# Power.net
KiCad netlist of a schematic drawn in Altium Designer
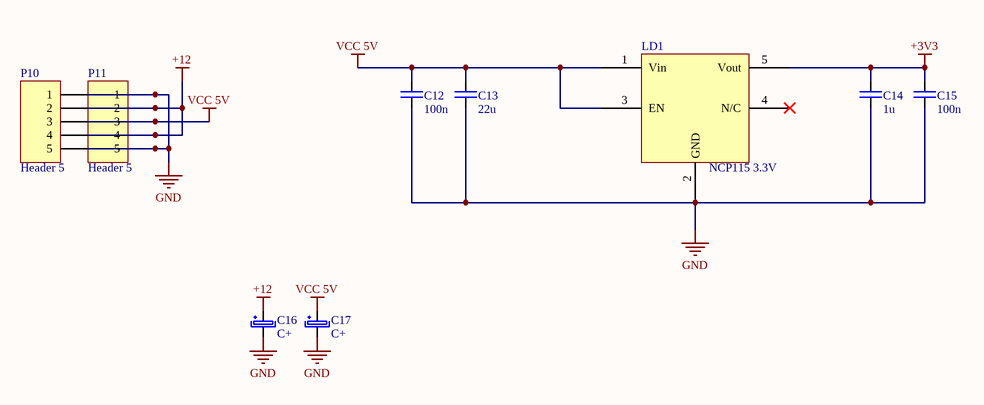
[diagram p0: Power.SchDoc]

(export (version "E")
  (design (tool "Eeschema 10.0.6"))
  (components
    (comp (ref "C12")
      (value "100n")
      (footprint "R1005_0402i_L")
      (description "Capacitor")
      (libsource (lib "General") (part "C"))
    )
    (comp (ref "C13")
      (value "22u")
      (footprint "C1608_0603I_L")
      (description "Capacitor")
      (libsource (lib "General") (part "C"))
    )
    (comp (ref "C14")
      (value "1u")
      (footprint "R1005_0402i_L")
      (description "Capacitor")
      (libsource (lib "General") (part "C"))
    )
    (comp (ref "C15")
      (value "100n")
      (footprint "R1005_0402i_L")
      (description "Capacitor")
      (libsource (lib "General") (part "C"))
    )
    (comp (ref "C16")
      (value "C+")
      (footprint "C AlElko 5x11 R2")
      (description "Capacitor Polarized")
      (libsource (lib "General") (part "C+"))
    )
    (comp (ref "C17")
      (value "C+")
      (footprint "C AlElko 5x11 R2")
      (description "Capacitor Polarized")
      (libsource (lib "General") (part "C+"))
    )
    (comp (ref "LD1")
      (value "NCP115 3.3V")
      (footprint "TSOP95P280X110-6L")
      (libsource (lib "components_library") (part "NCP115 3.3V"))
    )
    (comp (ref "P10")
      (value "Header 5")
      (footprint "HDR1X5")
      (description "Header, 5-Pin")
      (fields (field (name "PUBLISHER") "Altium Limited"))
      (libsource (lib "Miscellaneous Connectors") (part "Header 5"))
    )
    (comp (ref "P11")
      (value "Header 5")
      (footprint "HDR1X5")
      (description "Header, 5-Pin")
      (fields (field (name "PUBLISHER") "Altium Limited"))
      (libsource (lib "Miscellaneous Connectors") (part "Header 5"))
    )
  )
  (nets
    (net (code "1") (name "+3V3") (class "Default")
      (node (ref "C14") (pin "1") (pinfunction "1_1") (pintype "passive"))
      (node (ref "C15") (pin "1") (pinfunction "1_1") (pintype "passive"))
      (node (ref "LD1") (pin "5") (pinfunction "Vout_5") (pintype "passive"))
    )
    (net (code "2") (name "+12") (class "Default")
      (node (ref "C16") (pin "1") (pinfunction "1_1") (pintype "passive"))
      (node (ref "P10") (pin "2") (pinfunction "2_2") (pintype "passive"))
      (node (ref "P10") (pin "4") (pinfunction "4_4") (pintype "passive"))
      (node (ref "P11") (pin "2") (pinfunction "2_2") (pintype "passive"))
      (node (ref "P11") (pin "4") (pinfunction "4_4") (pintype "passive"))
    )
    (net (code "3") (name "GND") (class "Default")
      (node (ref "C12") (pin "2") (pinfunction "2_2") (pintype "passive"))
      (node (ref "C13") (pin "2") (pinfunction "2_2") (pintype "passive"))
      (node (ref "C14") (pin "2") (pinfunction "2_2") (pintype "passive"))
      (node (ref "C15") (pin "2") (pinfunction "2_2") (pintype "passive"))
      (node (ref "C16") (pin "2") (pinfunction "2_2") (pintype "passive"))
      (node (ref "C17") (pin "2") (pinfunction "2_2") (pintype "passive"))
      (node (ref "LD1") (pin "2") (pinfunction "GND_2") (pintype "passive"))
      (node (ref "P10") (pin "1") (pinfunction "1_1") (pintype "passive"))
      (node (ref "P10") (pin "5") (pinfunction "5_5") (pintype "passive"))
      (node (ref "P11") (pin "1") (pinfunction "1_1") (pintype "passive"))
      (node (ref "P11") (pin "5") (pinfunction "5_5") (pintype "passive"))
    )
    (net (code "4") (name "VCC 5V") (class "Default")
      (node (ref "C12") (pin "1") (pinfunction "1_1") (pintype "passive"))
      (node (ref "C13") (pin "1") (pinfunction "1_1") (pintype "passive"))
      (node (ref "C17") (pin "1") (pinfunction "1_1") (pintype "passive"))
      (node (ref "LD1") (pin "1") (pinfunction "Vin_1") (pintype "passive"))
      (node (ref "LD1") (pin "3") (pinfunction "EN_3") (pintype "passive"))
      (node (ref "P10") (pin "3") (pinfunction "3_3") (pintype "passive"))
      (node (ref "P11") (pin "3") (pinfunction "3_3") (pintype "passive"))
    )
    (net (code "5") (name "unconnected-(LD1-N{slash}C-Pad4)") (class "Default")
      (node (ref "LD1") (pin "4") (pinfunction "N/C_4") (pintype "passive+no_connect"))
    )
  )
)
